# CW308_IMXRT1062.net
KiCad netlist of a schematic drawn in Altium Designer
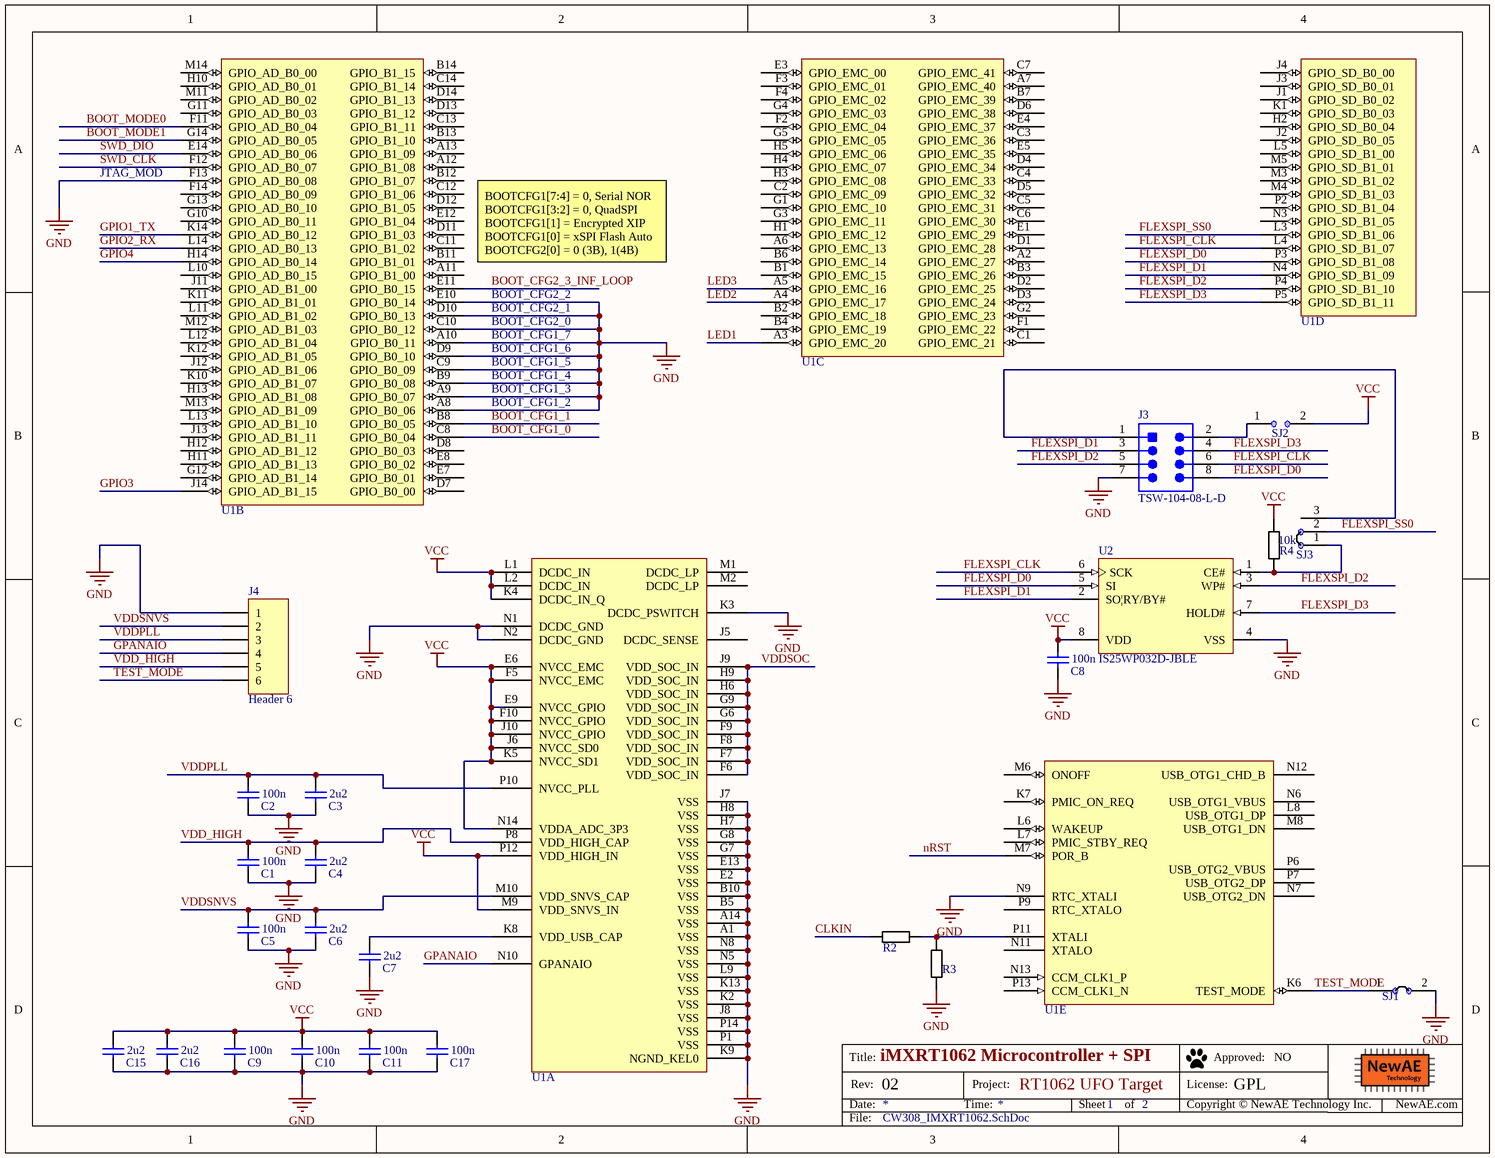
[diagram p0: CW308_IMXRT1062.SchDoc]

(export (version "E")
  (design (tool "Eeschema 10.0.6"))
  (components
    (comp (ref "C1")
      (value "100n")
      (footprint "CAPC0603_M")
      (description "100n, 0603")
      (fields (field (name "PART NUMBER") "CCHIP-100n-0603"))
      (libsource (lib "NewAE_AltiumLib") (part "CAP"))
    )
    (comp (ref "C2")
      (value "100n")
      (footprint "CAPC0603_M")
      (description "100n, 0603")
      (fields (field (name "PART NUMBER") "CCHIP-100n-0603"))
      (libsource (lib "NewAE_AltiumLib") (part "CAP"))
    )
    (comp (ref "C3")
      (value "2u2")
      (footprint "CAPC0603_M")
      (description "2u2, 0603")
      (fields (field (name "PART NUMBER") "CCHIP-2u2-0603"))
      (libsource (lib "NewAE_AltiumLib") (part "CAP"))
    )
    (comp (ref "C4")
      (value "2u2")
      (footprint "CAPC0603_M")
      (description "2u2, 0603")
      (fields (field (name "PART NUMBER") "CCHIP-2u2-0603"))
      (libsource (lib "NewAE_AltiumLib") (part "CAP"))
    )
    (comp (ref "C5")
      (value "100n")
      (footprint "CAPC0603_M")
      (description "100n, 0603")
      (fields (field (name "PART NUMBER") "CCHIP-100n-0603"))
      (libsource (lib "NewAE_AltiumLib") (part "CAP"))
    )
    (comp (ref "C6")
      (value "2u2")
      (footprint "CAPC0603_M")
      (description "2u2, 0603")
      (fields (field (name "PART NUMBER") "CCHIP-2u2-0603"))
      (libsource (lib "NewAE_AltiumLib") (part "CAP"))
    )
    (comp (ref "C7")
      (value "2u2")
      (footprint "CAPC0603_M")
      (description "2u2, 0603")
      (fields (field (name "PART NUMBER") "CCHIP-2u2-0603"))
      (libsource (lib "NewAE_AltiumLib") (part "CAP"))
    )
    (comp (ref "C8")
      (value "100n")
      (footprint "CAPC0603_M")
      (description "100n, 0603")
      (fields (field (name "PART NUMBER") "CCHIP-100n-0603"))
      (libsource (lib "NewAE_AltiumLib") (part "CAP"))
    )
    (comp (ref "C9")
      (value "100n")
      (footprint "CAPC0603_M")
      (description "100n, 0603")
      (fields (field (name "PART NUMBER") "CCHIP-100n-0603"))
      (libsource (lib "NewAE_AltiumLib") (part "CAP"))
    )
    (comp (ref "C10")
      (value "100n")
      (footprint "CAPC0603_M")
      (description "100n, 0603")
      (fields (field (name "PART NUMBER") "CCHIP-100n-0603"))
      (libsource (lib "NewAE_AltiumLib") (part "CAP"))
    )
    (comp (ref "C11")
      (value "100n")
      (footprint "CAPC0603_M")
      (description "100n, 0603")
      (fields (field (name "PART NUMBER") "CCHIP-100n-0603"))
      (libsource (lib "NewAE_AltiumLib") (part "CAP"))
    )
    (comp (ref "C15")
      (value "2u2")
      (footprint "CAPC0603_M")
      (description "2u2, 0603")
      (fields (field (name "PART NUMBER") "CCHIP-2u2-0603"))
      (libsource (lib "NewAE_AltiumLib") (part "CAP"))
    )
    (comp (ref "C16")
      (value "2u2")
      (footprint "CAPC0603_M")
      (description "2u2, 0603")
      (fields (field (name "PART NUMBER") "CCHIP-2u2-0603"))
      (libsource (lib "NewAE_AltiumLib") (part "CAP"))
    )
    (comp (ref "C17")
      (value "100n")
      (footprint "CAPC0603_M")
      (description "100n, 0603")
      (fields (field (name "PART NUMBER") "CCHIP-100n-0603"))
      (libsource (lib "NewAE_AltiumLib") (part "CAP"))
    )
    (comp (ref "J3")
      (value "TSW-104-08-L-D")
      (footprint "SMTC-TSW-104-08-L-D_V")
      (fields (field (name "MANUFACTURER") "Samtec"))
      (libsource (lib "Altium Content Vault") (part "CN-2P-M-R8"))
    )
    (comp (ref "J4")
      (value "Header 6")
      (footprint "HDR1X6")
      (description "Header, 6-Pin")
      (fields (field (name "PUBLISHER") "Altium Limited"))
      (libsource (lib "Miscellaneous Connectors") (part "Header 6"))
    )
    (comp (ref "R2")
      (value "100R")
      (footprint "RESC1608X55N")
      (description "100R res, 0603, 1%, 1/10W")
      (fields (field (name "PART NUMBER") "RCHIP-100R-0603") (field (name "TOLERANCE") "1%"))
      (libsource (lib "") (part "RES-EU_1"))
    )
    (comp (ref "R3")
      (value "33R")
      (footprint "RESC1608X55N")
      (description "33R res, 0603, 1%, 1/10W")
      (fields (field (name "PART NUMBER") "RCHIP-33R-0603") (field (name "TOLERANCE") "1%"))
      (libsource (lib "NewAE_AltiumLib") (part "RES-EU"))
    )
    (comp (ref "R4")
      (value "10k")
      (footprint "RESC1608X55N")
      (description "10k res, 0603, 1%, 1/10W")
      (fields (field (name "PART NUMBER") "RCHIP-10K-0603") (field (name "TOLERANCE") "1%"))
      (libsource (lib "NewAE_AltiumLib") (part "RES-EU"))
    )
    (comp (ref "SJ1")
      (value "NC")
      (footprint "SJ_2S_NC")
      (description "Solder Jumper, NC")
      (fields (field (name "PART NUMBER") "SJ_2S"))
      (libsource (lib "NewAE_AltiumLib") (part "SJ_2S"))
    )
    (comp (ref "SJ2")
      (value "NO")
      (footprint "SJ_2S_NO")
      (description "Solder Jumper, NO")
      (fields (field (name "PART NUMBER") "SJ_2S_NO"))
      (libsource (lib "NewAE_AltiumLib") (part "SJ_2S_NO"))
    )
    (comp (ref "SJ3")
      (value "NC")
      (footprint "SJ_3S_NC12")
      (description "Solder Jumper, NC")
      (fields (field (name "PART NUMBER") "SJ_3S_12JMP"))
      (libsource (lib "NewAE_AltiumLib") (part "SJ_3S_12JMP"))
    )
    (comp (ref "U1")
      (value "MIMXRT1062DVJ6A")
      (footprint "BGA196C80P14X14_1200X1200X161")
      (description "NXP Cross-Over iMX Microcontroller")
      (libsource (lib "NewAE_AltiumLib") (part "MIMXRT1062DVJ6A"))
    )
    (comp (ref "U2")
      (value "IS25WP032D-JBLE")
      (footprint "SOIC8_WIDE_NARROW")
      (description "32MB QPI/QPI/QSPI 8-PIN SOP 208M")
      (libsource (lib "NewAE_AltiumLib") (part "MCHP-SST25VFXXXB-SOIX-8"))
    )
  )
  (nets
    (net (code "1") (name "/BOOT_CFG1_0") (class "Default")
      (node (ref "U1") (pin "C8") (pinfunction "GPIO_B0_04_C8") (pintype "bidirectional"))
    )
    (net (code "2") (name "/BOOT_CFG1_1") (class "Default")
      (node (ref "U1") (pin "B8") (pinfunction "GPIO_B0_05_B8") (pintype "bidirectional"))
    )
    (net (code "3") (name "/BOOT_CFG2_3_INF_LOOP") (class "Default")
      (node (ref "U1") (pin "E11") (pinfunction "GPIO_B0_15_E11") (pintype "bidirectional"))
    )
    (net (code "4") (name "/BOOT_MODE0") (class "Default")
      (node (ref "U1") (pin "F11") (pinfunction "GPIO_AD_B0_04_F11") (pintype "bidirectional"))
    )
    (net (code "5") (name "/BOOT_MODE1") (class "Default")
      (node (ref "U1") (pin "G14") (pinfunction "GPIO_AD_B0_05_G14") (pintype "bidirectional"))
    )
    (net (code "6") (name "/CLKIN") (class "Default")
      (node (ref "R2") (pin "1") (pinfunction "1_1") (pintype "passive"))
    )
    (net (code "7") (name "/FLEXSPI_CLK") (class "Default")
      (node (ref "J3") (pin "6") (pinfunction "6_6") (pintype "passive"))
      (node (ref "U1") (pin "L4") (pinfunction "GPIO_SD_B1_07_L4") (pintype "bidirectional"))
      (node (ref "U2") (pin "6") (pinfunction "SCK_6") (pintype "input"))
    )
    (net (code "8") (name "/FLEXSPI_D0") (class "Default")
      (node (ref "J3") (pin "8") (pinfunction "8_8") (pintype "passive"))
      (node (ref "U1") (pin "P3") (pinfunction "GPIO_SD_B1_08_P3") (pintype "bidirectional"))
      (node (ref "U2") (pin "5") (pinfunction "SI_5") (pintype "input"))
    )
    (net (code "9") (name "/FLEXSPI_D1") (class "Default")
      (node (ref "J3") (pin "3") (pinfunction "3_3") (pintype "passive"))
      (node (ref "U1") (pin "N4") (pinfunction "GPIO_SD_B1_09_N4") (pintype "bidirectional"))
      (node (ref "U2") (pin "2") (pinfunction "SO¦RY/BY#_2") (pintype "tri_state"))
    )
    (net (code "10") (name "/FLEXSPI_D2") (class "Default")
      (node (ref "J3") (pin "5") (pinfunction "5_5") (pintype "passive"))
      (node (ref "U1") (pin "P4") (pinfunction "GPIO_SD_B1_10_P4") (pintype "bidirectional"))
      (node (ref "U2") (pin "3") (pinfunction "WP#_3") (pintype "input"))
    )
    (net (code "11") (name "/FLEXSPI_D3") (class "Default")
      (node (ref "J3") (pin "4") (pinfunction "4_4") (pintype "passive"))
      (node (ref "U1") (pin "P5") (pinfunction "GPIO_SD_B1_11_P5") (pintype "bidirectional"))
      (node (ref "U2") (pin "7") (pinfunction "HOLD#_7") (pintype "input"))
    )
    (net (code "12") (name "/FLEXSPI_SS0") (class "Default")
      (node (ref "SJ3") (pin "2") (pinfunction "2_2") (pintype "passive"))
      (node (ref "U1") (pin "L3") (pinfunction "GPIO_SD_B1_06_L3") (pintype "bidirectional"))
    )
    (net (code "13") (name "/GPANAIO") (class "Default")
      (node (ref "J4") (pin "4") (pinfunction "4_4") (pintype "passive"))
      (node (ref "U1") (pin "N10") (pinfunction "GPANAIO_N10") (pintype "passive"))
    )
    (net (code "14") (name "/GPIO1_TX") (class "Default")
      (node (ref "U1") (pin "K14") (pinfunction "GPIO_AD_B0_12_K14") (pintype "bidirectional"))
    )
    (net (code "15") (name "/GPIO2_RX") (class "Default")
      (node (ref "U1") (pin "L14") (pinfunction "GPIO_AD_B0_13_L14") (pintype "bidirectional"))
    )
    (net (code "16") (name "/GPIO3") (class "Default")
      (node (ref "U1") (pin "J14") (pinfunction "GPIO_AD_B1_15_J14") (pintype "bidirectional"))
    )
    (net (code "17") (name "/GPIO4") (class "Default")
      (node (ref "U1") (pin "H14") (pinfunction "GPIO_AD_B0_14_H14") (pintype "bidirectional"))
    )
    (net (code "18") (name "/LED1") (class "Default")
      (node (ref "U1") (pin "A3") (pinfunction "GPIO_EMC_20_A3") (pintype "bidirectional"))
    )
    (net (code "19") (name "/LED2") (class "Default")
      (node (ref "U1") (pin "A4") (pinfunction "GPIO_EMC_17_A4") (pintype "bidirectional"))
    )
    (net (code "20") (name "/LED3") (class "Default")
      (node (ref "U1") (pin "A5") (pinfunction "GPIO_EMC_16_A5") (pintype "bidirectional"))
    )
    (net (code "21") (name "/SWD_CLK") (class "Default")
      (node (ref "U1") (pin "F12") (pinfunction "GPIO_AD_B0_07_F12") (pintype "bidirectional"))
    )
    (net (code "22") (name "/SWD_DIO") (class "Default")
      (node (ref "U1") (pin "E14") (pinfunction "GPIO_AD_B0_06_E14") (pintype "bidirectional"))
    )
    (net (code "23") (name "/TEST_MODE") (class "Default")
      (node (ref "J4") (pin "6") (pinfunction "6_6") (pintype "passive"))
      (node (ref "SJ1") (pin "1") (pinfunction "1_1") (pintype "passive"))
      (node (ref "U1") (pin "K6") (pinfunction "TEST_MODE_K6") (pintype "bidirectional"))
    )
    (net (code "24") (name "/VDDPLL") (class "Default")
      (node (ref "C2") (pin "1") (pinfunction "1_1") (pintype "passive"))
      (node (ref "C3") (pin "1") (pinfunction "1_1") (pintype "passive"))
      (node (ref "J4") (pin "3") (pinfunction "3_3") (pintype "passive"))
      (node (ref "U1") (pin "P10") (pinfunction "NVCC_PLL_P10") (pintype "power_in"))
    )
    (net (code "25") (name "/VDDSNVS") (class "Default")
      (node (ref "C5") (pin "1") (pinfunction "1_1") (pintype "passive"))
      (node (ref "C6") (pin "1") (pinfunction "1_1") (pintype "passive"))
      (node (ref "J4") (pin "2") (pinfunction "2_2") (pintype "passive"))
      (node (ref "U1") (pin "M10") (pinfunction "VDD_SNVS_CAP_M10") (pintype "power_in"))
    )
    (net (code "26") (name "/VDDSOC") (class "Default")
      (node (ref "U1") (pin "F6") (pinfunction "VDD_SOC_IN_F6") (pintype "power_in"))
      (node (ref "U1") (pin "F7") (pinfunction "VDD_SOC_IN_F7") (pintype "power_in"))
      (node (ref "U1") (pin "F8") (pinfunction "VDD_SOC_IN_F8") (pintype "power_in"))
      (node (ref "U1") (pin "F9") (pinfunction "VDD_SOC_IN_F9") (pintype "power_in"))
      (node (ref "U1") (pin "G6") (pinfunction "VDD_SOC_IN_G6") (pintype "power_in"))
      (node (ref "U1") (pin "G9") (pinfunction "VDD_SOC_IN_G9") (pintype "power_in"))
      (node (ref "U1") (pin "H6") (pinfunction "VDD_SOC_IN_H6") (pintype "power_in"))
      (node (ref "U1") (pin "H9") (pinfunction "VDD_SOC_IN_H9") (pintype "power_in"))
      (node (ref "U1") (pin "J9") (pinfunction "VDD_SOC_IN_J9") (pintype "power_in"))
    )
    (net (code "27") (name "/VDD_HIGH") (class "Default")
      (node (ref "C1") (pin "1") (pinfunction "1_1") (pintype "passive"))
      (node (ref "C4") (pin "1") (pinfunction "1_1") (pintype "passive"))
      (node (ref "J4") (pin "5") (pinfunction "5_5") (pintype "passive"))
      (node (ref "U1") (pin "P8") (pinfunction "VDD_HIGH_CAP_P8") (pintype "power_in"))
    )
    (net (code "28") (name "/nRST") (class "Default")
      (node (ref "U1") (pin "M7") (pinfunction "POR_B_M7") (pintype "bidirectional"))
    )
    (net (code "29") (name "GND") (class "Default")
      (node (ref "C1") (pin "2") (pinfunction "2_2") (pintype "passive"))
      (node (ref "C10") (pin "2") (pinfunction "2_2") (pintype "passive"))
      (node (ref "C11") (pin "2") (pinfunction "2_2") (pintype "passive"))
      (node (ref "C15") (pin "2") (pinfunction "2_2") (pintype "passive"))
      (node (ref "C16") (pin "2") (pinfunction "2_2") (pintype "passive"))
      (node (ref "C17") (pin "2") (pinfunction "2_2") (pintype "passive"))
      (node (ref "C2") (pin "2") (pinfunction "2_2") (pintype "passive"))
      (node (ref "C3") (pin "2") (pinfunction "2_2") (pintype "passive"))
      (node (ref "C4") (pin "2") (pinfunction "2_2") (pintype "passive"))
      (node (ref "C5") (pin "2") (pinfunction "2_2") (pintype "passive"))
      (node (ref "C6") (pin "2") (pinfunction "2_2") (pintype "passive"))
      (node (ref "C7") (pin "2") (pinfunction "2_2") (pintype "passive"))
      (node (ref "C8") (pin "2") (pinfunction "2_2") (pintype "passive"))
      (node (ref "C9") (pin "2") (pinfunction "2_2") (pintype "passive"))
      (node (ref "J3") (pin "7") (pinfunction "7_7") (pintype "passive"))
      (node (ref "J4") (pin "1") (pinfunction "1_1") (pintype "passive"))
      (node (ref "R3") (pin "2") (pinfunction "2_2") (pintype "passive"))
      (node (ref "SJ1") (pin "2") (pinfunction "2_2") (pintype "passive"))
      (node (ref "U1") (pin "A1") (pinfunction "VSS_A1") (pintype "power_in"))
      (node (ref "U1") (pin "A10") (pinfunction "GPIO_B0_11_A10") (pintype "bidirectional"))
      (node (ref "U1") (pin "A14") (pinfunction "VSS_A14") (pintype "power_in"))
      (node (ref "U1") (pin "A8") (pinfunction "GPIO_B0_06_A8") (pintype "bidirectional"))
      (node (ref "U1") (pin "A9") (pinfunction "GPIO_B0_07_A9") (pintype "bidirectional"))
      (node (ref "U1") (pin "B10") (pinfunction "VSS_B10") (pintype "power_in"))
      (node (ref "U1") (pin "B5") (pinfunction "VSS_B5") (pintype "power_in"))
      (node (ref "U1") (pin "B9") (pinfunction "GPIO_B0_08_B9") (pintype "bidirectional"))
      (node (ref "U1") (pin "C10") (pinfunction "GPIO_B0_12_C10") (pintype "bidirectional"))
      (node (ref "U1") (pin "C9") (pinfunction "GPIO_B0_09_C9") (pintype "bidirectional"))
      (node (ref "U1") (pin "D10") (pinfunction "GPIO_B0_13_D10") (pintype "bidirectional"))
      (node (ref "U1") (pin "D9") (pinfunction "GPIO_B0_10_D9") (pintype "bidirectional"))
      (node (ref "U1") (pin "E10") (pinfunction "GPIO_B0_14_E10") (pintype "bidirectional"))
      (node (ref "U1") (pin "E13") (pinfunction "VSS_E13") (pintype "power_in"))
      (node (ref "U1") (pin "E2") (pinfunction "VSS_E2") (pintype "power_in"))
      (node (ref "U1") (pin "F13") (pinfunction "GPIO_AD_B0_08_F13") (pintype "bidirectional"))
      (node (ref "U1") (pin "G7") (pinfunction "VSS_G7") (pintype "power_in"))
      (node (ref "U1") (pin "G8") (pinfunction "VSS_G8") (pintype "power_in"))
      (node (ref "U1") (pin "H7") (pinfunction "VSS_H7") (pintype "power_in"))
      (node (ref "U1") (pin "H8") (pinfunction "VSS_H8") (pintype "power_in"))
      (node (ref "U1") (pin "J7") (pinfunction "VSS_J7") (pintype "power_in"))
      (node (ref "U1") (pin "J8") (pinfunction "VSS_J8") (pintype "power_in"))
      (node (ref "U1") (pin "K13") (pinfunction "VSS_K13") (pintype "power_in"))
      (node (ref "U1") (pin "K2") (pinfunction "VSS_K2") (pintype "power_in"))
      (node (ref "U1") (pin "K3") (pinfunction "DCDC_PSWITCH_K3") (pintype "passive"))
      (node (ref "U1") (pin "K9") (pinfunction "NGND_KEL0_K9") (pintype "power_in"))
      (node (ref "U1") (pin "L9") (pinfunction "VSS_L9") (pintype "power_in"))
      (node (ref "U1") (pin "N1") (pinfunction "DCDC_GND_N1") (pintype "passive"))
      (node (ref "U1") (pin "N2") (pinfunction "DCDC_GND_N2") (pintype "passive"))
      (node (ref "U1") (pin "N5") (pinfunction "VSS_N5") (pintype "power_in"))
      (node (ref "U1") (pin "N8") (pinfunction "VSS_N8") (pintype "power_in"))
      (node (ref "U1") (pin "N9") (pinfunction "RTC_XTALI_N9") (pintype "passive"))
      (node (ref "U1") (pin "P1") (pinfunction "VSS_P1") (pintype "power_in"))
      (node (ref "U1") (pin "P14") (pinfunction "VSS_P14") (pintype "power_in"))
      (node (ref "U2") (pin "4") (pinfunction "VSS_4") (pintype "power_in"))
    )
    (net (code "30") (name "Net-(J3-Pad1)") (class "Default")
      (node (ref "J3") (pin "1") (pinfunction "1_1") (pintype "passive"))
      (node (ref "SJ3") (pin "3") (pinfunction "3_3") (pintype "passive"))
    )
    (net (code "31") (name "Net-(J3-Pad2)") (class "Default")
      (node (ref "J3") (pin "2") (pinfunction "2_2") (pintype "passive"))
      (node (ref "SJ2") (pin "1") (pinfunction "1_1") (pintype "passive"))
    )
    (net (code "32") (name "Net-(U1A-VDD_USB_CAP)") (class "Default")
      (node (ref "C7") (pin "1") (pinfunction "1_1") (pintype "passive"))
      (node (ref "U1") (pin "K8") (pinfunction "VDD_USB_CAP_K8") (pintype "power_in"))
    )
    (net (code "33") (name "Net-(U1E-XTALI)") (class "Default")
      (node (ref "R2") (pin "2") (pinfunction "2_2") (pintype "passive"))
      (node (ref "R3") (pin "1") (pinfunction "1_1") (pintype "passive"))
      (node (ref "U1") (pin "P11") (pinfunction "XTALI_P11") (pintype "passive"))
    )
    (net (code "34") (name "Net-(U2-CE#)") (class "Default")
      (node (ref "R4") (pin "2") (pinfunction "2_2") (pintype "passive"))
      (node (ref "SJ3") (pin "1") (pinfunction "1_1") (pintype "passive"))
      (node (ref "U2") (pin "1") (pinfunction "CE#_1") (pintype "input"))
    )
    (net (code "35") (name "VCC") (class "Default")
      (node (ref "C10") (pin "1") (pinfunction "1_1") (pintype "passive"))
      (node (ref "C11") (pin "1") (pinfunction "1_1") (pintype "passive"))
      (node (ref "C15") (pin "1") (pinfunction "1_1") (pintype "passive"))
      (node (ref "C16") (pin "1") (pinfunction "1_1") (pintype "passive"))
      (node (ref "C17") (pin "1") (pinfunction "1_1") (pintype "passive"))
      (node (ref "C8") (pin "1") (pinfunction "1_1") (pintype "passive"))
      (node (ref "C9") (pin "1") (pinfunction "1_1") (pintype "passive"))
      (node (ref "R4") (pin "1") (pinfunction "1_1") (pintype "passive"))
      (node (ref "SJ2") (pin "2") (pinfunction "2_2") (pintype "passive"))
      (node (ref "U1") (pin "E6") (pinfunction "NVCC_EMC_E6") (pintype "power_in"))
      (node (ref "U1") (pin "E9") (pinfunction "NVCC_GPIO_E9") (pintype "power_in"))
      (node (ref "U1") (pin "F10") (pinfunction "NVCC_GPIO_F10") (pintype "power_in"))
      (node (ref "U1") (pin "F5") (pinfunction "NVCC_EMC_F5") (pintype "power_in"))
      (node (ref "U1") (pin "J10") (pinfunction "NVCC_GPIO_J10") (pintype "power_in"))
      (node (ref "U1") (pin "J6") (pinfunction "NVCC_SD0_J6") (pintype "power_in"))
      (node (ref "U1") (pin "K4") (pinfunction "DCDC_IN_Q_K4") (pintype "passive"))
      (node (ref "U1") (pin "K5") (pinfunction "NVCC_SD1_K5") (pintype "power_in"))
      (node (ref "U1") (pin "L1") (pinfunction "DCDC_IN_L1") (pintype "passive"))
      (node (ref "U1") (pin "L2") (pinfunction "DCDC_IN_L2") (pintype "passive"))
      (node (ref "U1") (pin "M9") (pinfunction "VDD_SNVS_IN_M9") (pintype "power_in"))
      (node (ref "U1") (pin "N14") (pinfunction "VDDA_ADC_3P3_N14") (pintype "power_in"))
      (node (ref "U1") (pin "P12") (pinfunction "VDD_HIGH_IN_P12") (pintype "power_in"))
      (node (ref "U2") (pin "8") (pinfunction "VDD_8") (pintype "power_in"))
    )
    (net (code "36") (name "unconnected-(U1A-DCDC_LP-PadM1)") (class "Default")
      (node (ref "U1") (pin "M1") (pinfunction "DCDC_LP_M1") (pintype "passive"))
    )
    (net (code "37") (name "unconnected-(U1A-DCDC_LP-PadM2)") (class "Default")
      (node (ref "U1") (pin "M2") (pinfunction "DCDC_LP_M2") (pintype "passive"))
    )
    (net (code "38") (name "unconnected-(U1A-DCDC_SENSE-PadJ5)") (class "Default")
      (node (ref "U1") (pin "J5") (pinfunction "DCDC_SENSE_J5") (pintype "passive"))
    )
    (net (code "39") (name "unconnected-(U1B-GPIO_AD_B0_00-PadM14)") (class "Default")
      (node (ref "U1") (pin "M14") (pinfunction "GPIO_AD_B0_00_M14") (pintype "bidirectional"))
    )
    (net (code "40") (name "unconnected-(U1B-GPIO_AD_B0_01-PadH10)") (class "Default")
      (node (ref "U1") (pin "H10") (pinfunction "GPIO_AD_B0_01_H10") (pintype "bidirectional"))
    )
    (net (code "41") (name "unconnected-(U1B-GPIO_AD_B0_02-PadM11)") (class "Default")
      (node (ref "U1") (pin "M11") (pinfunction "GPIO_AD_B0_02_M11") (pintype "bidirectional"))
    )
    (net (code "42") (name "unconnected-(U1B-GPIO_AD_B0_03-PadG11)") (class "Default")
      (node (ref "U1") (pin "G11") (pinfunction "GPIO_AD_B0_03_G11") (pintype "bidirectional"))
    )
    (net (code "43") (name "unconnected-(U1B-GPIO_AD_B0_09-PadF14)") (class "Default")
      (node (ref "U1") (pin "F14") (pinfunction "GPIO_AD_B0_09_F14") (pintype "bidirectional"))
    )
    (net (code "44") (name "unconnected-(U1B-GPIO_AD_B0_10-PadG13)") (class "Default")
      (node (ref "U1") (pin "G13") (pinfunction "GPIO_AD_B0_10_G13") (pintype "bidirectional"))
    )
    (net (code "45") (name "unconnected-(U1B-GPIO_AD_B0_11-PadG10)") (class "Default")
      (node (ref "U1") (pin "G10") (pinfunction "GPIO_AD_B0_11_G10") (pintype "bidirectional"))
    )
    (net (code "46") (name "unconnected-(U1B-GPIO_AD_B0_15-PadL10)") (class "Default")
      (node (ref "U1") (pin "L10") (pinfunction "GPIO_AD_B0_15_L10") (pintype "bidirectional"))
    )
    (net (code "47") (name "unconnected-(U1B-GPIO_AD_B1_00-PadJ11)") (class "Default")
      (node (ref "U1") (pin "J11") (pinfunction "GPIO_AD_B1_00_J11") (pintype "bidirectional"))
    )
    (net (code "48") (name "unconnected-(U1B-GPIO_AD_B1_01-PadK11)") (class "Default")
      (node (ref "U1") (pin "K11") (pinfunction "GPIO_AD_B1_01_K11") (pintype "bidirectional"))
    )
    (net (code "49") (name "unconnected-(U1B-GPIO_AD_B1_02-PadL11)") (class "Default")
      (node (ref "U1") (pin "L11") (pinfunction "GPIO_AD_B1_02_L11") (pintype "bidirectional"))
    )
    (net (code "50") (name "unconnected-(U1B-GPIO_AD_B1_03-PadM12)") (class "Default")
      (node (ref "U1") (pin "M12") (pinfunction "GPIO_AD_B1_03_M12") (pintype "bidirectional"))
    )
    (net (code "51") (name "unconnected-(U1B-GPIO_AD_B1_04-PadL12)") (class "Default")
      (node (ref "U1") (pin "L12") (pinfunction "GPIO_AD_B1_04_L12") (pintype "bidirectional"))
    )
    (net (code "52") (name "unconnected-(U1B-GPIO_AD_B1_05-PadK12)") (class "Default")
      (node (ref "U1") (pin "K12") (pinfunction "GPIO_AD_B1_05_K12") (pintype "bidirectional"))
    )
    (net (code "53") (name "unconnected-(U1B-GPIO_AD_B1_06-PadJ12)") (class "Default")
      (node (ref "U1") (pin "J12") (pinfunction "GPIO_AD_B1_06_J12") (pintype "bidirectional"))
    )
    (net (code "54") (name "unconnected-(U1B-GPIO_AD_B1_07-PadK10)") (class "Default")
      (node (ref "U1") (pin "K10") (pinfunction "GPIO_AD_B1_07_K10") (pintype "bidirectional"))
    )
    (net (code "55") (name "unconnected-(U1B-GPIO_AD_B1_08-PadH13)") (class "Default")
      (node (ref "U1") (pin "H13") (pinfunction "GPIO_AD_B1_08_H13") (pintype "bidirectional"))
    )
    (net (code "56") (name "unconnected-(U1B-GPIO_AD_B1_09-PadM13)") (class "Default")
      (node (ref "U1") (pin "M13") (pinfunction "GPIO_AD_B1_09_M13") (pintype "bidirectional"))
    )
    (net (code "57") (name "unconnected-(U1B-GPIO_AD_B1_10-PadL13)") (class "Default")
      (node (ref "U1") (pin "L13") (pinfunction "GPIO_AD_B1_10_L13") (pintype "bidirectional"))
    )
    (net (code "58") (name "unconnected-(U1B-GPIO_AD_B1_11-PadJ13)") (class "Default")
      (node (ref "U1") (pin "J13") (pinfunction "GPIO_AD_B1_11_J13") (pintype "bidirectional"))
    )
    (net (code "59") (name "unconnected-(U1B-GPIO_AD_B1_12-PadH12)") (class "Default")
      (node (ref "U1") (pin "H12") (pinfunction "GPIO_AD_B1_12_H12") (pintype "bidirectional"))
    )
    (net (code "60") (name "unconnected-(U1B-GPIO_AD_B1_13-PadH11)") (class "Default")
      (node (ref "U1") (pin "H11") (pinfunction "GPIO_AD_B1_13_H11") (pintype "bidirectional"))
    )
    (net (code "61") (name "unconnected-(U1B-GPIO_AD_B1_14-PadG12)") (class "Default")
      (node (ref "U1") (pin "G12") (pinfunction "GPIO_AD_B1_14_G12") (pintype "bidirectional"))
    )
    (net (code "62") (name "unconnected-(U1B-GPIO_B0_00-PadD7)") (class "Default")
      (node (ref "U1") (pin "D7") (pinfunction "GPIO_B0_00_D7") (pintype "bidirectional"))
    )
    (net (code "63") (name "unconnected-(U1B-GPIO_B0_01-PadE7)") (class "Default")
      (node (ref "U1") (pin "E7") (pinfunction "GPIO_B0_01_E7") (pintype "bidirectional"))
    )
    (net (code "64") (name "unconnected-(U1B-GPIO_B0_02-PadE8)") (class "Default")
      (node (ref "U1") (pin "E8") (pinfunction "GPIO_B0_02_E8") (pintype "bidirectional"))
    )
    (net (code "65") (name "unconnected-(U1B-GPIO_B0_03-PadD8)") (class "Default")
      (node (ref "U1") (pin "D8") (pinfunction "GPIO_B0_03_D8") (pintype "bidirectional"))
    )
    (net (code "66") (name "unconnected-(U1B-GPIO_B1_00-PadA11)") (class "Default")
      (node (ref "U1") (pin "A11") (pinfunction "GPIO_B1_00_A11") (pintype "bidirectional"))
    )
    (net (code "67") (name "unconnected-(U1B-GPIO_B1_01-PadB11)") (class "Default")
      (node (ref "U1") (pin "B11") (pinfunction "GPIO_B1_01_B11") (pintype "bidirectional"))
    )
    (net (code "68") (name "unconnected-(U1B-GPIO_B1_02-PadC11)") (class "Default")
      (node (ref "U1") (pin "C11") (pinfunction "GPIO_B1_02_C11") (pintype "bidirectional"))
    )
    (net (code "69") (name "unconnected-(U1B-GPIO_B1_03-PadD11)") (class "Default")
      (node (ref "U1") (pin "D11") (pinfunction "GPIO_B1_03_D11") (pintype "bidirectional"))
    )
    (net (code "70") (name "unconnected-(U1B-GPIO_B1_04-PadE12)") (class "Default")
      (node (ref "U1") (pin "E12") (pinfunction "GPIO_B1_04_E12") (pintype "bidirectional"))
    )
    (net (code "71") (name "unconnected-(U1B-GPIO_B1_05-PadD12)") (class "Default")
      (node (ref "U1") (pin "D12") (pinfunction "GPIO_B1_05_D12") (pintype "bidirectional"))
    )
    (net (code "72") (name "unconnected-(U1B-GPIO_B1_06-PadC12)") (class "Default")
      (node (ref "U1") (pin "C12") (pinfunction "GPIO_B1_06_C12") (pintype "bidirectional"))
    )
    (net (code "73") (name "unconnected-(U1B-GPIO_B1_07-PadB12)") (class "Default")
      (node (ref "U1") (pin "B12") (pinfunction "GPIO_B1_07_B12") (pintype "bidirectional"))
    )
    (net (code "74") (name "unconnected-(U1B-GPIO_B1_08-PadA12)") (class "Default")
      (node (ref "U1") (pin "A12") (pinfunction "GPIO_B1_08_A12") (pintype "bidirectional"))
    )
    (net (code "75") (name "unconnected-(U1B-GPIO_B1_09-PadA13)") (class "Default")
      (node (ref "U1") (pin "A13") (pinfunction "GPIO_B1_09_A13") (pintype "bidirectional"))
    )
    (net (code "76") (name "unconnected-(U1B-GPIO_B1_10-PadB13)") (class "Default")
      (node (ref "U1") (pin "B13") (pinfunction "GPIO_B1_10_B13") (pintype "bidirectional"))
    )
    (net (code "77") (name "unconnected-(U1B-GPIO_B1_11-PadC13)") (class "Default")
      (node (ref "U1") (pin "C13") (pinfunction "GPIO_B1_11_C13") (pintype "bidirectional"))
    )
    (net (code "78") (name "unconnected-(U1B-GPIO_B1_12-PadD13)") (class "Default")
      (node (ref "U1") (pin "D13") (pinfunction "GPIO_B1_12_D13") (pintype "bidirectional"))
    )
    (net (code "79") (name "unconnected-(U1B-GPIO_B1_13-PadD14)") (class "Default")
      (node (ref "U1") (pin "D14") (pinfunction "GPIO_B1_13_D14") (pintype "bidirectional"))
    )
    (net (code "80") (name "unconnected-(U1B-GPIO_B1_14-PadC14)") (class "Default")
      (node (ref "U1") (pin "C14") (pinfunction "GPIO_B1_14_C14") (pintype "bidirectional"))
    )
    (net (code "81") (name "unconnected-(U1B-GPIO_B1_15-PadB14)") (class "Default")
      (node (ref "U1") (pin "B14") (pinfunction "GPIO_B1_15_B14") (pintype "bidirectional"))
    )
    (net (code "82") (name "unconnected-(U1C-GPIO_EMC_00-PadE3)") (class "Default")
      (node (ref "U1") (pin "E3") (pinfunction "GPIO_EMC_00_E3") (pintype "bidirectional"))
    )
    (net (code "83") (name "unconnected-(U1C-GPIO_EMC_01-PadF3)") (class "Default")
      (node (ref "U1") (pin "F3") (pinfunction "GPIO_EMC_01_F3") (pintype "bidirectional"))
    )
    (net (code "84") (name "unconnected-(U1C-GPIO_EMC_02-PadF4)") (class "Default")
      (node (ref "U1") (pin "F4") (pinfunction "GPIO_EMC_02_F4") (pintype "bidirectional"))
    )
    (net (code "85") (name "unconnected-(U1C-GPIO_EMC_03-PadG4)") (class "Default")
      (node (ref "U1") (pin "G4") (pinfunction "GPIO_EMC_03_G4") (pintype "bidirectional"))
    )
    (net (code "86") (name "unconnected-(U1C-GPIO_EMC_04-PadF2)") (class "Default")
      (node (ref "U1") (pin "F2") (pinfunction "GPIO_EMC_04_F2") (pintype "bidirectional"))
    )
    (net (code "87") (name "unconnected-(U1C-GPIO_EMC_05-PadG5)") (class "Default")
      (node (ref "U1") (pin "G5") (pinfunction "GPIO_EMC_05_G5") (pintype "bidirectional"))
    )
    (net (code "88") (name "unconnected-(U1C-GPIO_EMC_06-PadH5)") (class "Default")
      (node (ref "U1") (pin "H5") (pinfunction "GPIO_EMC_06_H5") (pintype "bidirectional"))
    )
    (net (code "89") (name "unconnected-(U1C-GPIO_EMC_07-PadH4)") (class "Default")
      (node (ref "U1") (pin "H4") (pinfunction "GPIO_EMC_07_H4") (pintype "bidirectional"))
    )
    (net (code "90") (name "unconnected-(U1C-GPIO_EMC_08-PadH3)") (class "Default")
      (node (ref "U1") (pin "H3") (pinfunction "GPIO_EMC_08_H3") (pintype "bidirectional"))
    )
    (net (code "91") (name "unconnected-(U1C-GPIO_EMC_09-PadC2)") (class "Default")
      (node (ref "U1") (pin "C2") (pinfunction "GPIO_EMC_09_C2") (pintype "bidirectional"))
    )
    (net (code "92") (name "unconnected-(U1C-GPIO_EMC_10-PadG1)") (class "Default")
      (node (ref "U1") (pin "G1") (pinfunction "GPIO_EMC_10_G1") (pintype "bidirectional"))
    )
    (net (code "93") (name "unconnected-(U1C-GPIO_EMC_11-PadG3)") (class "Default")
      (node (ref "U1") (pin "G3") (pinfunction "GPIO_EMC_11_G3") (pintype "bidirectional"))
    )
    (net (code "94") (name "unconnected-(U1C-GPIO_EMC_12-PadH1)") (class "Default")
      (node (ref "U1") (pin "H1") (pinfunction "GPIO_EMC_12_H1") (pintype "bidirectional"))
    )
    (net (code "95") (name "unconnected-(U1C-GPIO_EMC_13-PadA6)") (class "Default")
      (node (ref "U1") (pin "A6") (pinfunction "GPIO_EMC_13_A6") (pintype "bidirectional"))
    )
    (net (code "96") (name "unconnected-(U1C-GPIO_EMC_14-PadB6)") (class "Default")
      (node (ref "U1") (pin "B6") (pinfunction "GPIO_EMC_14_B6") (pintype "bidirectional"))
    )
    (net (code "97") (name "unconnected-(U1C-GPIO_EMC_15-PadB1)") (class "Default")
      (node (ref "U1") (pin "B1") (pinfunction "GPIO_EMC_15_B1") (pintype "bidirectional"))
    )
    (net (code "98") (name "unconnected-(U1C-GPIO_EMC_18-PadB2)") (class "Default")
      (node (ref "U1") (pin "B2") (pinfunction "GPIO_EMC_18_B2") (pintype "bidirectional"))
    )
    (net (code "99") (name "unconnected-(U1C-GPIO_EMC_19-PadB4)") (class "Default")
      (node (ref "U1") (pin "B4") (pinfunction "GPIO_EMC_19_B4") (pintype "bidirectional"))
    )
    (net (code "100") (name "unconnected-(U1C-GPIO_EMC_21-PadC1)") (class "Default")
      (node (ref "U1") (pin "C1") (pinfunction "GPIO_EMC_21_C1") (pintype "bidirectional"))
    )
    (net (code "101") (name "unconnected-(U1C-GPIO_EMC_22-PadF1)") (class "Default")
      (node (ref "U1") (pin "F1") (pinfunction "GPIO_EMC_22_F1") (pintype "bidirectional"))
    )
    (net (code "102") (name "unconnected-(U1C-GPIO_EMC_23-PadG2)") (class "Default")
      (node (ref "U1") (pin "G2") (pinfunction "GPIO_EMC_23_G2") (pintype "bidirectional"))
    )
    (net (code "103") (name "unconnected-(U1C-GPIO_EMC_24-PadD3)") (class "Default")
      (node (ref "U1") (pin "D3") (pinfunction "GPIO_EMC_24_D3") (pintype "bidirectional"))
    )
    (net (code "104") (name "unconnected-(U1C-GPIO_EMC_25-PadD2)") (class "Default")
      (node (ref "U1") (pin "D2") (pinfunction "GPIO_EMC_25_D2") (pintype "bidirectional"))
    )
    (net (code "105") (name "unconnected-(U1C-GPIO_EMC_26-PadB3)") (class "Default")
      (node (ref "U1") (pin "B3") (pinfunction "GPIO_EMC_26_B3") (pintype "bidirectional"))
    )
    (net (code "106") (name "unconnected-(U1C-GPIO_EMC_27-PadA2)") (class "Default")
      (node (ref "U1") (pin "A2") (pinfunction "GPIO_EMC_27_A2") (pintype "bidirectional"))
    )
    (net (code "107") (name "unconnected-(U1C-GPIO_EMC_28-PadD1)") (class "Default")
      (node (ref "U1") (pin "D1") (pinfunction "GPIO_EMC_28_D1") (pintype "bidirectional"))
    )
    (net (code "108") (name "unconnected-(U1C-GPIO_EMC_29-PadE1)") (class "Default")
      (node (ref "U1") (pin "E1") (pinfunction "GPIO_EMC_29_E1") (pintype "bidirectional"))
    )
    (net (code "109") (name "unconnected-(U1C-GPIO_EMC_30-PadC6)") (class "Default")
      (node (ref "U1") (pin "C6") (pinfunction "GPIO_EMC_30_C6") (pintype "bidirectional"))
    )
    (net (code "110") (name "unconnected-(U1C-GPIO_EMC_31-PadC5)") (class "Default")
      (node (ref "U1") (pin "C5") (pinfunction "GPIO_EMC_31_C5") (pintype "bidirectional"))
    )
    (net (code "111") (name "unconnected-(U1C-GPIO_EMC_32-PadD5)") (class "Default")
      (node (ref "U1") (pin "D5") (pinfunction "GPIO_EMC_32_D5") (pintype "bidirectional"))
    )
    (net (code "112") (name "unconnected-(U1C-GPIO_EMC_33-PadC4)") (class "Default")
      (node (ref "U1") (pin "C4") (pinfunction "GPIO_EMC_33_C4") (pintype "bidirectional"))
    )
    (net (code "113") (name "unconnected-(U1C-GPIO_EMC_34-PadD4)") (class "Default")
      (node (ref "U1") (pin "D4") (pinfunction "GPIO_EMC_34_D4") (pintype "bidirectional"))
    )
    (net (code "114") (name "unconnected-(U1C-GPIO_EMC_35-PadE5)") (class "Default")
      (node (ref "U1") (pin "E5") (pinfunction "GPIO_EMC_35_E5") (pintype "bidirectional"))
    )
    (net (code "115") (name "unconnected-(U1C-GPIO_EMC_36-PadC3)") (class "Default")
      (node (ref "U1") (pin "C3") (pinfunction "GPIO_EMC_36_C3") (pintype "bidirectional"))
    )
    (net (code "116") (name "unconnected-(U1C-GPIO_EMC_37-PadE4)") (class "Default")
      (node (ref "U1") (pin "E4") (pinfunction "GPIO_EMC_37_E4") (pintype "bidirectional"))
    )
    (net (code "117") (name "unconnected-(U1C-GPIO_EMC_38-PadD6)") (class "Default")
      (node (ref "U1") (pin "D6") (pinfunction "GPIO_EMC_38_D6") (pintype "bidirectional"))
    )
    (net (code "118") (name "unconnected-(U1C-GPIO_EMC_39-PadB7)") (class "Default")
      (node (ref "U1") (pin "B7") (pinfunction "GPIO_EMC_39_B7") (pintype "bidirectional"))
    )
    (net (code "119") (name "unconnected-(U1C-GPIO_EMC_40-PadA7)") (class "Default")
      (node (ref "U1") (pin "A7") (pinfunction "GPIO_EMC_40_A7") (pintype "bidirectional"))
    )
    (net (code "120") (name "unconnected-(U1C-GPIO_EMC_41-PadC7)") (class "Default")
      (node (ref "U1") (pin "C7") (pinfunction "GPIO_EMC_41_C7") (pintype "bidirectional"))
    )
    (net (code "121") (name "unconnected-(U1D-GPIO_SD_B0_00-PadJ4)") (class "Default")
      (node (ref "U1") (pin "J4") (pinfunction "GPIO_SD_B0_00_J4") (pintype "bidirectional"))
    )
    (net (code "122") (name "unconnected-(U1D-GPIO_SD_B0_01-PadJ3)") (class "Default")
      (node (ref "U1") (pin "J3") (pinfunction "GPIO_SD_B0_01_J3") (pintype "bidirectional"))
    )
    (net (code "123") (name "unconnected-(U1D-GPIO_SD_B0_02-PadJ1)") (class "Default")
      (node (ref "U1") (pin "J1") (pinfunction "GPIO_SD_B0_02_J1") (pintype "bidirectional"))
    )
    (net (code "124") (name "unconnected-(U1D-GPIO_SD_B0_03-PadK1)") (class "Default")
      (node (ref "U1") (pin "K1") (pinfunction "GPIO_SD_B0_03_K1") (pintype "bidirectional"))
    )
    (net (code "125") (name "unconnected-(U1D-GPIO_SD_B0_04-PadH2)") (class "Default")
      (node (ref "U1") (pin "H2") (pinfunction "GPIO_SD_B0_04_H2") (pintype "bidirectional"))
    )
    (net (code "126") (name "unconnected-(U1D-GPIO_SD_B0_05-PadJ2)") (class "Default")
      (node (ref "U1") (pin "J2") (pinfunction "GPIO_SD_B0_05_J2") (pintype "bidirectional"))
    )
    (net (code "127") (name "unconnected-(U1D-GPIO_SD_B1_00-PadL5)") (class "Default")
      (node (ref "U1") (pin "L5") (pinfunction "GPIO_SD_B1_00_L5") (pintype "bidirectional"))
    )
    (net (code "128") (name "unconnected-(U1D-GPIO_SD_B1_01-PadM5)") (class "Default")
      (node (ref "U1") (pin "M5") (pinfunction "GPIO_SD_B1_01_M5") (pintype "bidirectional"))
    )
    (net (code "129") (name "unconnected-(U1D-GPIO_SD_B1_02-PadM3)") (class "Default")
      (node (ref "U1") (pin "M3") (pinfunction "GPIO_SD_B1_02_M3") (pintype "bidirectional"))
    )
    (net (code "130") (name "unconnected-(U1D-GPIO_SD_B1_03-PadM4)") (class "Default")
      (node (ref "U1") (pin "M4") (pinfunction "GPIO_SD_B1_03_M4") (pintype "bidirectional"))
    )
    (net (code "131") (name "unconnected-(U1D-GPIO_SD_B1_04-PadP2)") (class "Default")
      (node (ref "U1") (pin "P2") (pinfunction "GPIO_SD_B1_04_P2") (pintype "bidirectional"))
    )
    (net (code "132") (name "unconnected-(U1D-GPIO_SD_B1_05-PadN3)") (class "Default")
      (node (ref "U1") (pin "N3") (pinfunction "GPIO_SD_B1_05_N3") (pintype "bidirectional"))
    )
    (net (code "133") (name "unconnected-(U1E-CCM_CLK1_N-PadP13)") (class "Default")
      (node (ref "U1") (pin "P13") (pinfunction "CCM_CLK1_N_P13") (pintype "input"))
    )
    (net (code "134") (name "unconnected-(U1E-CCM_CLK1_P-PadN13)") (class "Default")
      (node (ref "U1") (pin "N13") (pinfunction "CCM_CLK1_P_N13") (pintype "input"))
    )
    (net (code "135") (name "unconnected-(U1E-ONOFF-PadM6)") (class "Default")
      (node (ref "U1") (pin "M6") (pinfunction "ONOFF_M6") (pintype "bidirectional"))
    )
    (net (code "136") (name "unconnected-(U1E-PMIC_ON_REQ-PadK7)") (class "Default")
      (node (ref "U1") (pin "K7") (pinfunction "PMIC_ON_REQ_K7") (pintype "bidirectional"))
    )
    (net (code "137") (name "unconnected-(U1E-PMIC_STBY_REQ-PadL7)") (class "Default")
      (node (ref "U1") (pin "L7") (pinfunction "PMIC_STBY_REQ_L7") (pintype "bidirectional"))
    )
    (net (code "138") (name "unconnected-(U1E-RTC_XTALO-PadP9)") (class "Default")
      (node (ref "U1") (pin "P9") (pinfunction "RTC_XTALO_P9") (pintype "passive"))
    )
    (net (code "139") (name "unconnected-(U1E-USB_OTG1_CHD_B-PadN12)") (class "Default")
      (node (ref "U1") (pin "N12") (pinfunction "USB_OTG1_CHD_B_N12") (pintype "passive"))
    )
    (net (code "140") (name "unconnected-(U1E-USB_OTG1_DN-PadM8)") (class "Default")
      (node (ref "U1") (pin "M8") (pinfunction "USB_OTG1_DN_M8") (pintype "passive"))
    )
    (net (code "141") (name "unconnected-(U1E-USB_OTG1_DP-PadL8)") (class "Default")
      (node (ref "U1") (pin "L8") (pinfunction "USB_OTG1_DP_L8") (pintype "passive"))
    )
    (net (code "142") (name "unconnected-(U1E-USB_OTG1_VBUS-PadN6)") (class "Default")
      (node (ref "U1") (pin "N6") (pinfunction "USB_OTG1_VBUS_N6") (pintype "passive"))
    )
    (net (code "143") (name "unconnected-(U1E-USB_OTG2_DN-PadN7)") (class "Default")
      (node (ref "U1") (pin "N7") (pinfunction "USB_OTG2_DN_N7") (pintype "passive"))
    )
    (net (code "144") (name "unconnected-(U1E-USB_OTG2_DP-PadP7)") (class "Default")
      (node (ref "U1") (pin "P7") (pinfunction "USB_OTG2_DP_P7") (pintype "passive"))
    )
    (net (code "145") (name "unconnected-(U1E-USB_OTG2_VBUS-PadP6)") (class "Default")
      (node (ref "U1") (pin "P6") (pinfunction "USB_OTG2_VBUS_P6") (pintype "passive"))
    )
    (net (code "146") (name "unconnected-(U1E-WAKEUP-PadL6)") (class "Default")
      (node (ref "U1") (pin "L6") (pinfunction "WAKEUP_L6") (pintype "bidirectional"))
    )
    (net (code "147") (name "unconnected-(U1E-XTALO-PadN11)") (class "Default")
      (node (ref "U1") (pin "N11") (pinfunction "XTALO_N11") (pintype "passive"))
    )
  )
)
